# ProcessorTestBoardV2.net
KiCad netlist of a schematic drawn in EAGLE
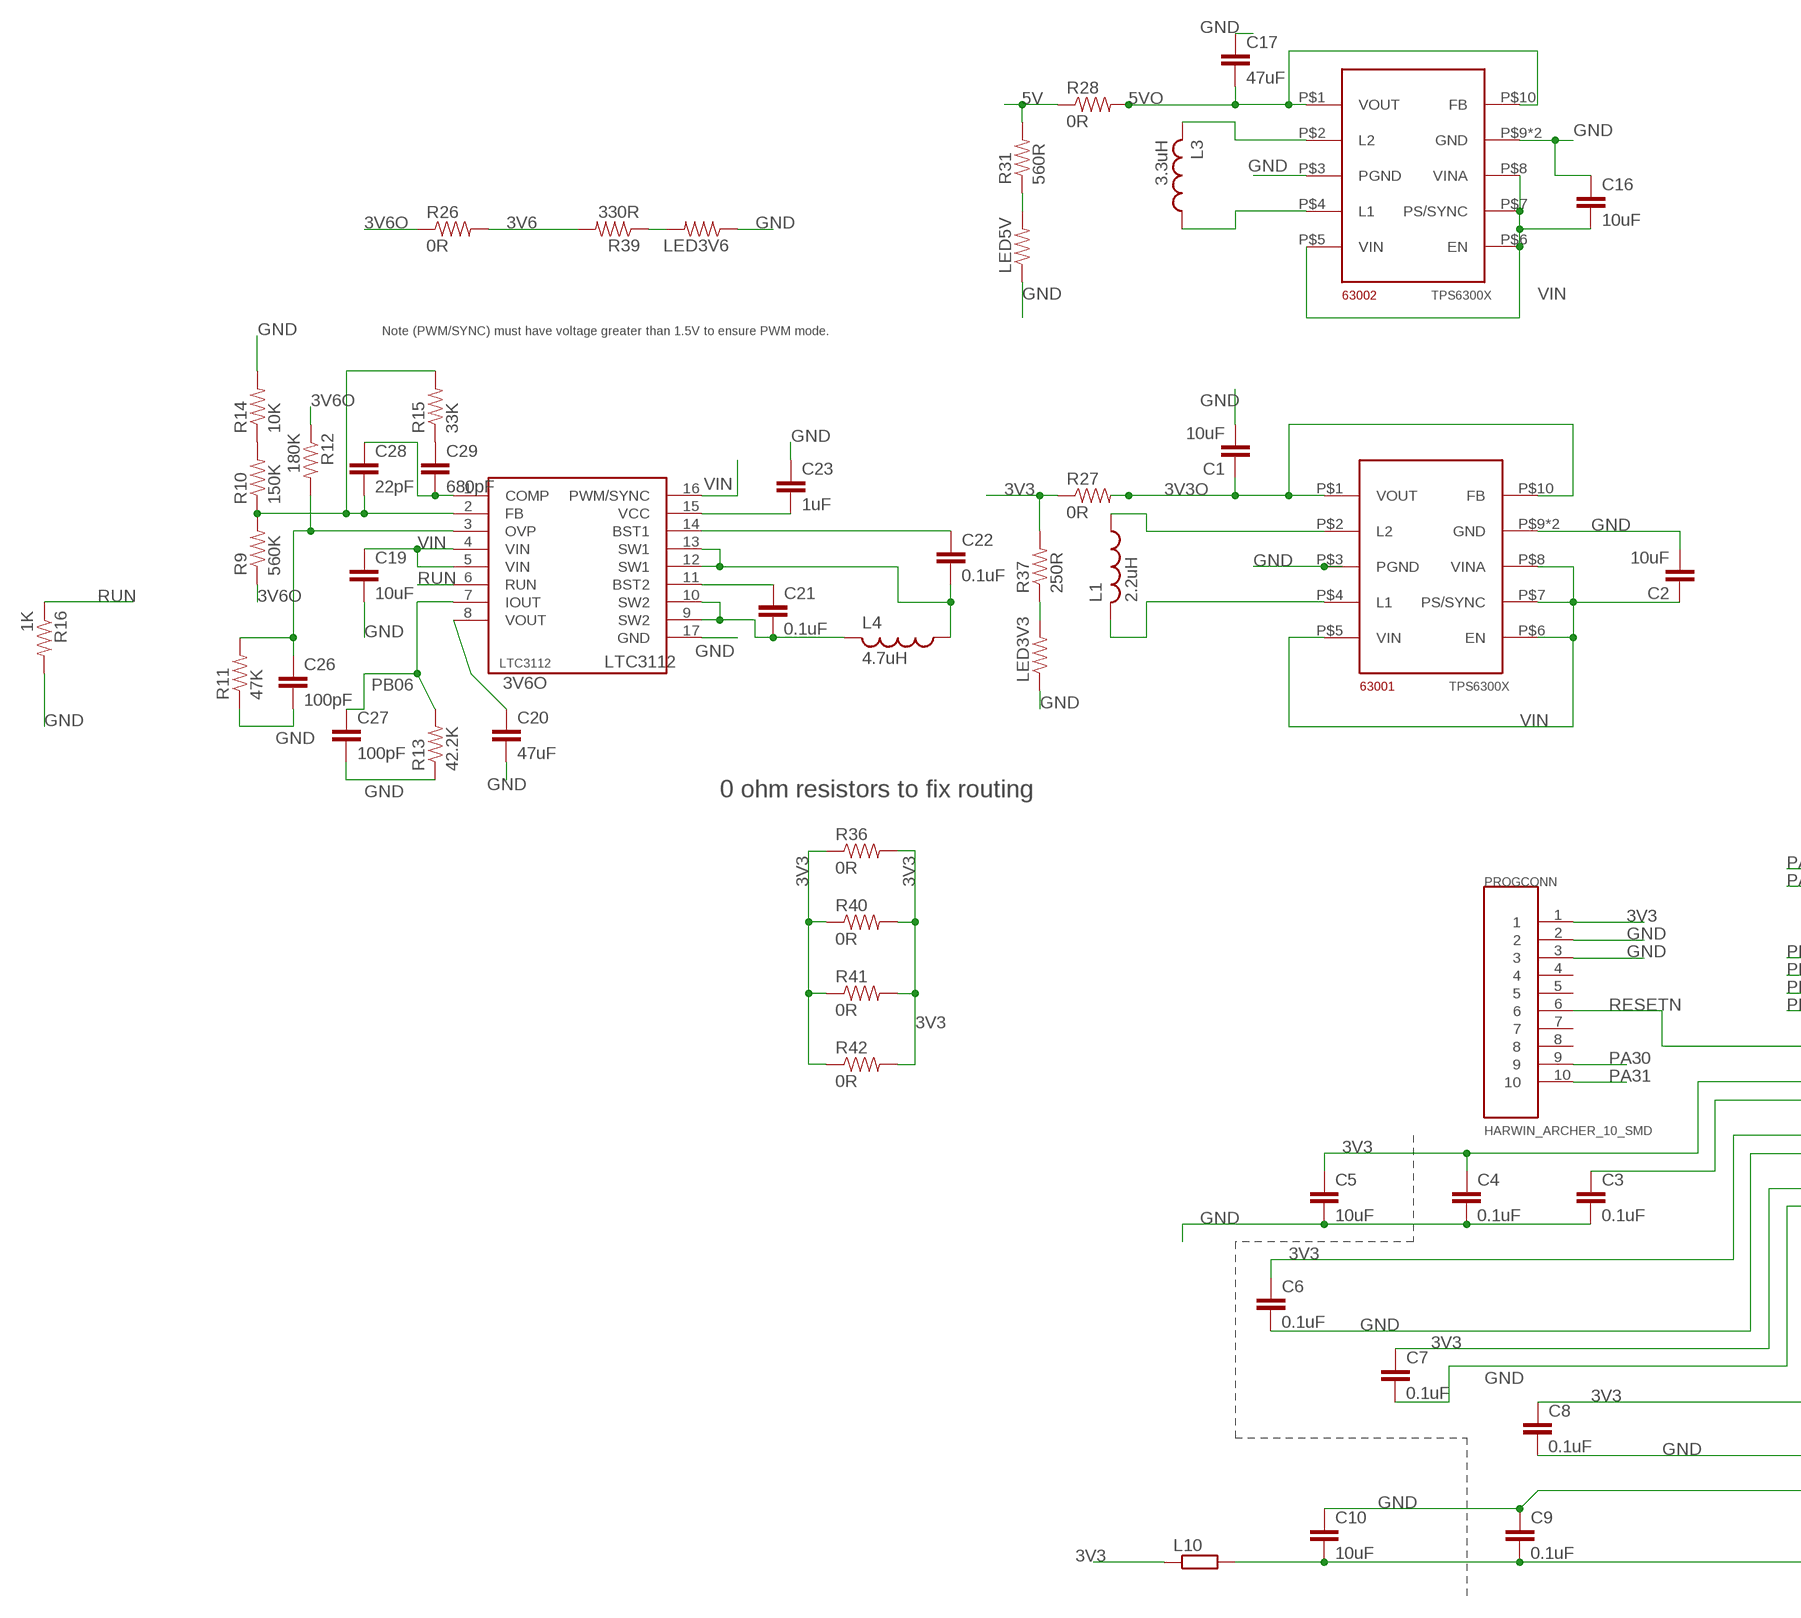
[diagram p0: schematic, sheet 1, part 1 of 2]
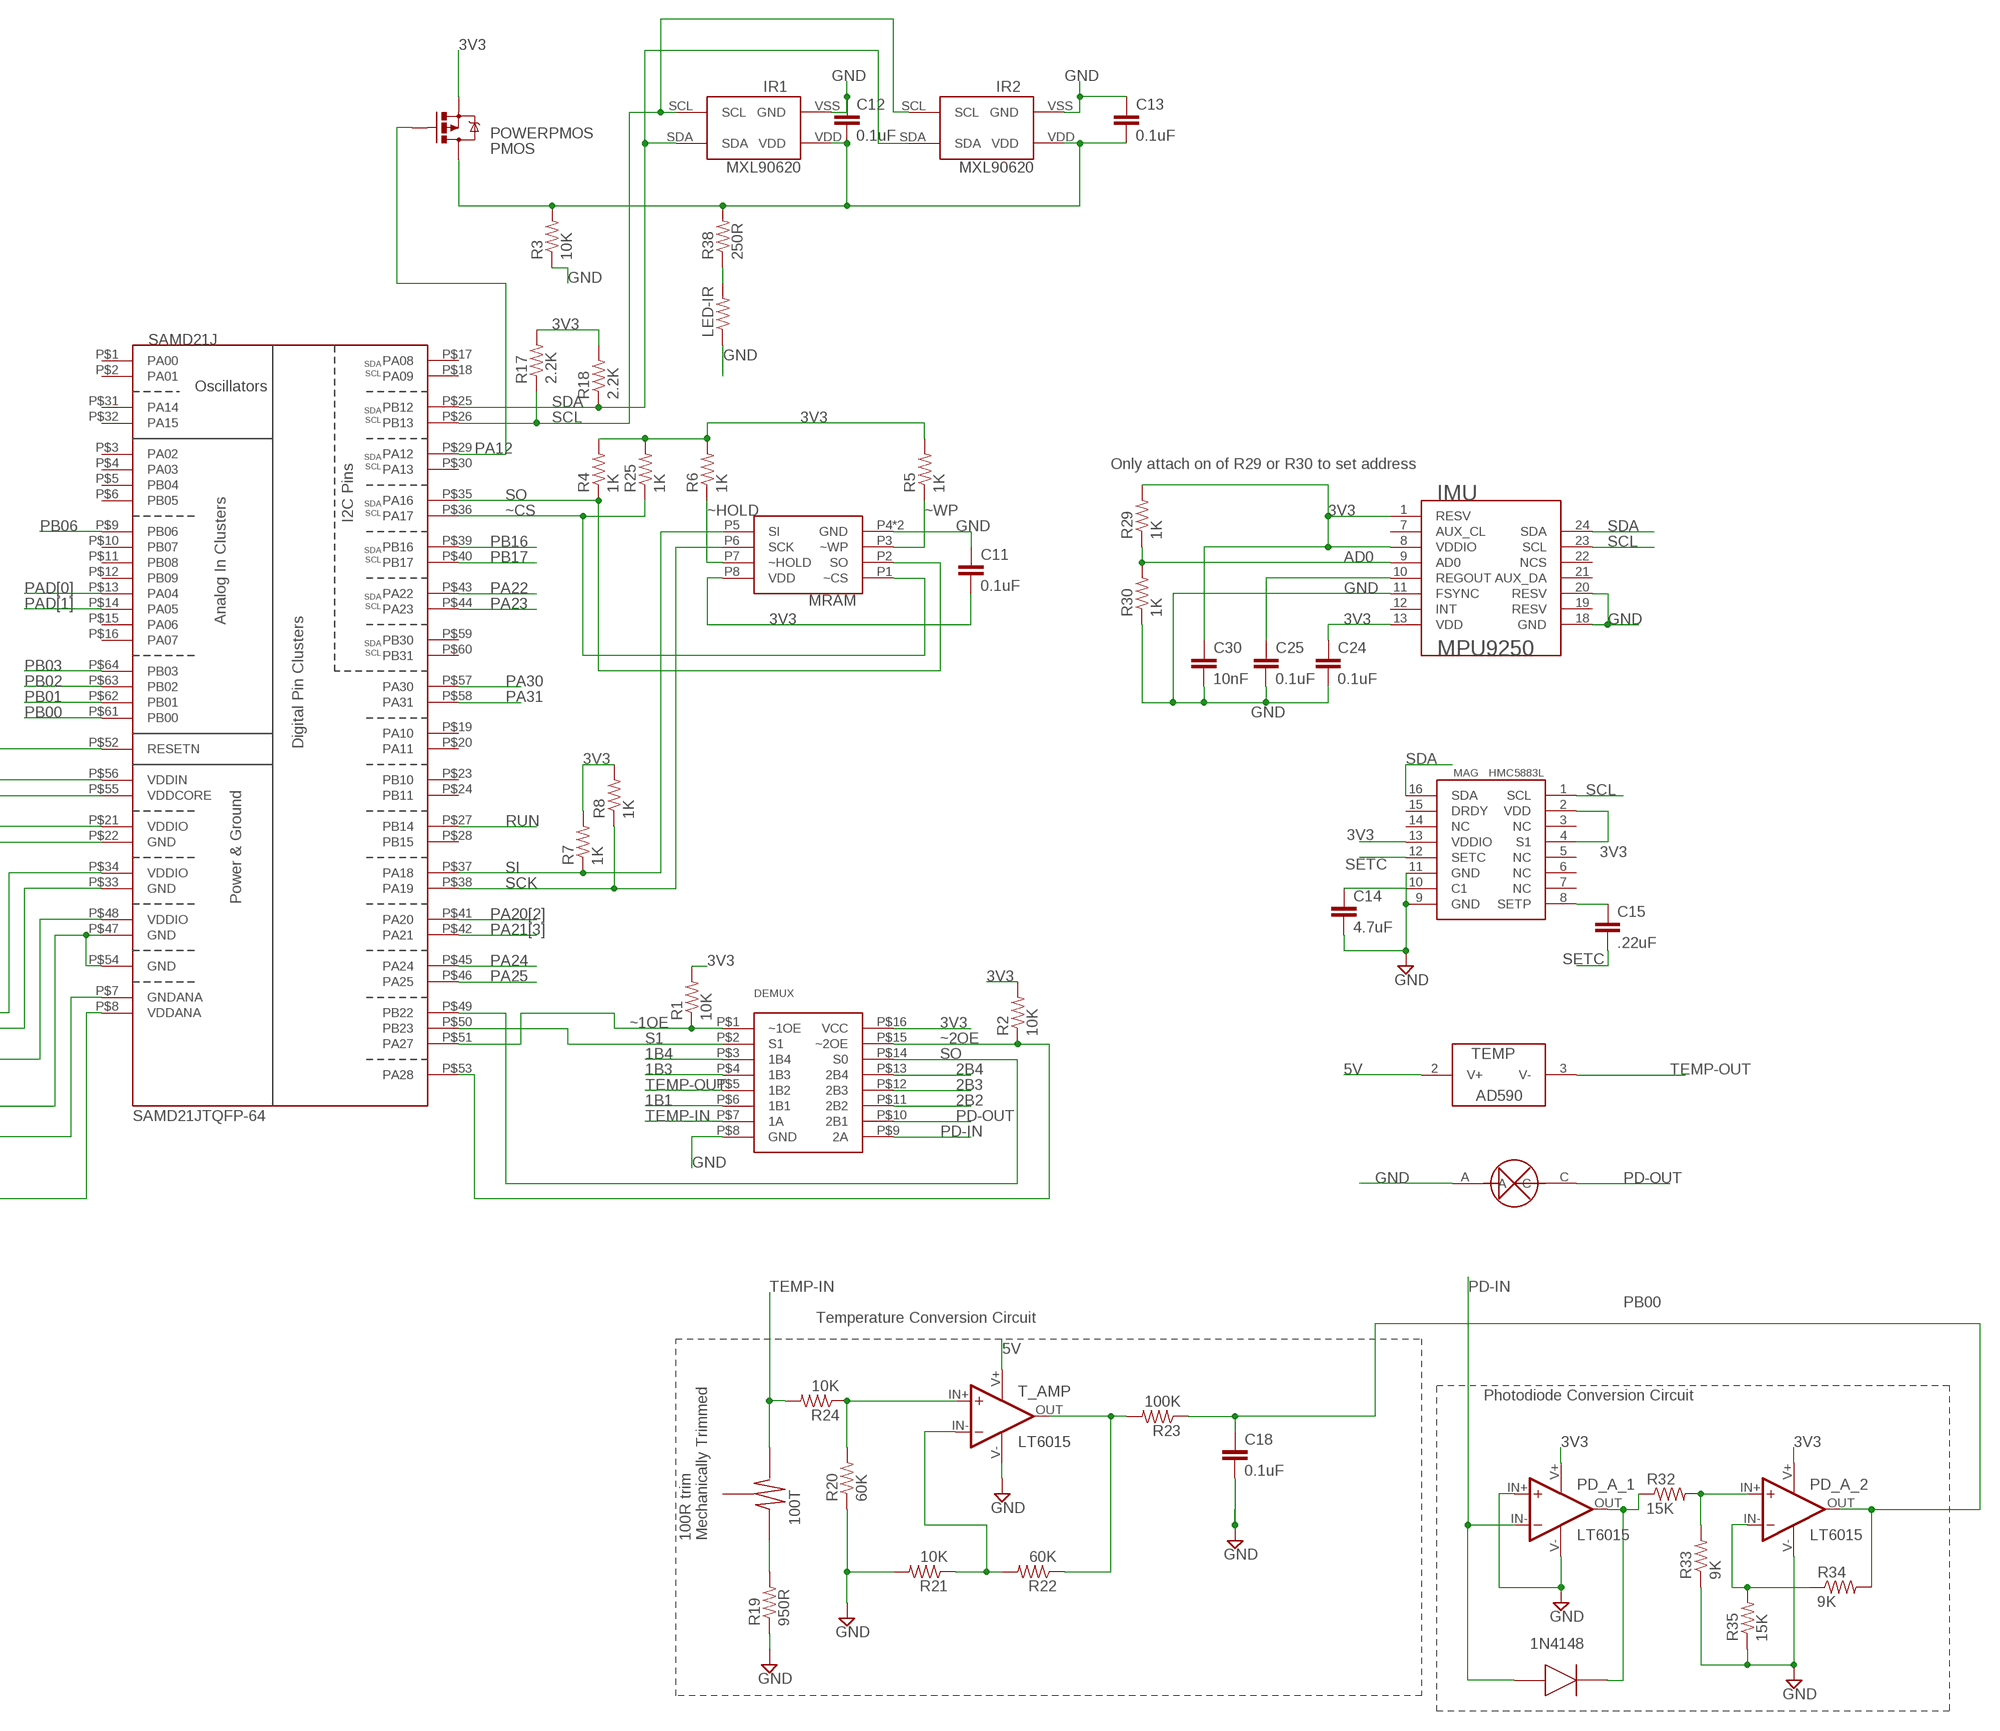
[diagram p1: schematic, sheet 1, part 2 of 2]

(export (version "E")
  (design (tool "Eeschema 10.0.6"))
  (components
    (comp (ref "1N4148")
      (value "1N4148WS")
      (footprint "eagle-import:SOD-323F")
      (libsource (lib "eagle-import") (part "1N4148WS"))
    )
    (comp (ref "100T")
      (value "TRIMPOT-TC33")
      (footprint "eagle-import:TC33X-2")
      (libsource (lib "eagle-import") (part "TRIMPOT-TC33"))
    )
    (comp (ref "63001")
      (value "TPS6300X")
      (footprint "eagle-import:QFN10_POWERPAD")
      (libsource (lib "eagle-import") (part "TPS6300X"))
    )
    (comp (ref "63002")
      (value "TPS6300X")
      (footprint "eagle-import:QFN10_POWERPAD")
      (libsource (lib "eagle-import") (part "TPS6300X"))
    )
    (comp (ref "C1")
      (value "10uF")
      (footprint "eagle-import:0805")
      (libsource (lib "eagle-import") (part "CAP0805"))
    )
    (comp (ref "C2")
      (value "10uF")
      (footprint "eagle-import:0805")
      (libsource (lib "eagle-import") (part "CAP0805"))
    )
    (comp (ref "C3")
      (value "0.1uF")
      (footprint "eagle-import:0805")
      (libsource (lib "eagle-import") (part "CAP0805"))
    )
    (comp (ref "C4")
      (value "0.1uF")
      (footprint "eagle-import:0805")
      (libsource (lib "eagle-import") (part "CAP0805"))
    )
    (comp (ref "C5")
      (value "10uF")
      (footprint "eagle-import:0805")
      (libsource (lib "eagle-import") (part "CAP0805"))
    )
    (comp (ref "C6")
      (value "0.1uF")
      (footprint "eagle-import:0805")
      (libsource (lib "eagle-import") (part "CAP0805"))
    )
    (comp (ref "C7")
      (value "0.1uF")
      (footprint "eagle-import:0805")
      (libsource (lib "eagle-import") (part "CAP0805"))
    )
    (comp (ref "C8")
      (value "0.1uF")
      (footprint "eagle-import:0805")
      (libsource (lib "eagle-import") (part "CAP0805"))
    )
    (comp (ref "C9")
      (value "0.1uF")
      (footprint "eagle-import:0805")
      (libsource (lib "eagle-import") (part "CAP0805"))
    )
    (comp (ref "C10")
      (value "10uF")
      (footprint "eagle-import:0805")
      (libsource (lib "eagle-import") (part "CAP0805"))
    )
    (comp (ref "C11")
      (value "0.1uF")
      (footprint "eagle-import:0805")
      (libsource (lib "eagle-import") (part "CAP0805"))
    )
    (comp (ref "C12")
      (value "0.1uF")
      (footprint "eagle-import:0805")
      (libsource (lib "eagle-import") (part "CAP0805"))
    )
    (comp (ref "C13")
      (value "0.1uF")
      (footprint "eagle-import:0805")
      (libsource (lib "eagle-import") (part "CAP0805"))
    )
    (comp (ref "C14")
      (value "4.7uF")
      (footprint "eagle-import:0805")
      (fields (field (name "MF") "AVX CORPORATION") (field (name "MPN") "08056D475KAT2A"))
      (libsource (lib "eagle-import") (part "CAP0805"))
    )
    (comp (ref "C15")
      (value ".22uF")
      (footprint "eagle-import:0805")
      (fields (field (name "MF") "AVX CORPORATION") (field (name "MPN") "08053C224KAT2A"))
      (libsource (lib "eagle-import") (part "CAP0805"))
    )
    (comp (ref "C16")
      (value "10uF")
      (footprint "eagle-import:0603-CAP")
      (fields (field (name "MPN") "C1608X5R1A225K080AC"))
      (libsource (lib "eagle-import") (part "CAP0603-CAP"))
    )
    (comp (ref "C17")
      (value "47uF")
      (footprint "eagle-import:0603-CAP")
      (fields (field (name "MPN") "EMK107B7474KA-T"))
      (libsource (lib "eagle-import") (part "CAP0603-CAP"))
    )
    (comp (ref "C18")
      (value "0.1uF")
      (footprint "eagle-import:0805")
      (libsource (lib "eagle-import") (part "CAP0805"))
    )
    (comp (ref "C19")
      (value "10uF")
      (footprint "eagle-import:0603-CAP")
      (libsource (lib "eagle-import") (part "CAP0603-CAP"))
    )
    (comp (ref "C20")
      (value "47uF")
      (footprint "eagle-import:0805")
      (fields (field (name "MPN") "EMK107B7474KA-T"))
      (libsource (lib "eagle-import") (part "CAP0805"))
    )
    (comp (ref "C21")
      (value "0.1uF")
      (footprint "eagle-import:0603-CAP")
      (fields (field (name "MPN") "0603YC104JAT2A"))
      (libsource (lib "eagle-import") (part "CAP0603-CAP"))
    )
    (comp (ref "C22")
      (value "0.1uF")
      (footprint "eagle-import:0603-CAP")
      (fields (field (name "MPN") "0603YC104JAT2A"))
      (libsource (lib "eagle-import") (part "CAP0603-CAP"))
    )
    (comp (ref "C23")
      (value "1uF")
      (footprint "eagle-import:0603-CAP")
      (libsource (lib "eagle-import") (part "CAP0603-CAP"))
    )
    (comp (ref "C24")
      (value "0.1uF")
      (footprint "eagle-import:0805")
      (libsource (lib "eagle-import") (part "CAP0805"))
    )
    (comp (ref "C25")
      (value "0.1uF")
      (footprint "eagle-import:0805")
      (libsource (lib "eagle-import") (part "CAP0805"))
    )
    (comp (ref "C26")
      (value "100pF")
      (footprint "eagle-import:0805")
      (fields (field (name "MF") "AVX CORPORATION") (field (name "MPN") "08051A101J4T4A"))
      (libsource (lib "eagle-import") (part "CAP0805"))
    )
    (comp (ref "C27")
      (value "100pF")
      (footprint "eagle-import:0805")
      (fields (field (name "MF") "AVX CORPORATION") (field (name "MPN") "08051A101J4T4A"))
      (libsource (lib "eagle-import") (part "CAP0805"))
    )
    (comp (ref "C28")
      (value "22pF")
      (footprint "eagle-import:0805")
      (fields (field (name "MF") "AVX CORPORATION") (field (name "MPN") "08051A220JAT2A"))
      (libsource (lib "eagle-import") (part "CAP0805"))
    )
    (comp (ref "C29")
      (value "680pF")
      (footprint "eagle-import:0805")
      (fields (field (name "MPN") "08055C681KAT2A"))
      (libsource (lib "eagle-import") (part "CAP0805"))
    )
    (comp (ref "C30")
      (value "10nF")
      (footprint "eagle-import:0805")
      (libsource (lib "eagle-import") (part "CAP0805"))
    )
    (comp (ref "DEMUX")
      (value "SN74CBTLV3253")
      (footprint "eagle-import:SOIC16R")
      (libsource (lib "eagle-import") (part "SN74CBTLV3253"))
    )
    (comp (ref "IMU")
      (value "MPU9250")
      (footprint "eagle-import:QFN-24-3X3")
      (libsource (lib "eagle-import") (part "MPU9250"))
    )
    (comp (ref "IR1")
      (value "MXL90620")
      (footprint "eagle-import:MXL90620")
      (libsource (lib "eagle-import") (part "MXL90620"))
    )
    (comp (ref "IR2")
      (value "MXL90620")
      (footprint "eagle-import:MXL90620")
      (libsource (lib "eagle-import") (part "MXL90620"))
    )
    (comp (ref "L1")
      (value "2.2uH")
      (footprint "eagle-import:L3225M")
      (libsource (lib "eagle-import") (part "L-USL3225M"))
    )
    (comp (ref "L3")
      (value "3.3uH")
      (footprint "eagle-import:L3225M")
      (fields (field (name "MPN") "JMK212BJ335KG-T"))
      (libsource (lib "eagle-import") (part "L-USL3225M"))
    )
    (comp (ref "L4")
      (value "4.7uH")
      (footprint "eagle-import:L3225M")
      (libsource (lib "eagle-import") (part "L-USL3225M"))
    )
    (comp (ref "L10")
      (value "R-EU_R0805")
      (footprint "eagle-import:R0805")
      (libsource (lib "eagle-import") (part "R-EU_R0805"))
    )
    (comp (ref "LED-IR")
      (value "RESISTOR")
      (footprint "eagle-import:0805")
      (libsource (lib "eagle-import") (part "RESISTOR"))
    )
    (comp (ref "LED3V3")
      (value "RESISTOR")
      (footprint "eagle-import:0805")
      (libsource (lib "eagle-import") (part "RESISTOR"))
    )
    (comp (ref "LED3V6")
      (value "RESISTOR")
      (footprint "eagle-import:0805")
      (libsource (lib "eagle-import") (part "RESISTOR"))
    )
    (comp (ref "LED5V")
      (value "RESISTOR")
      (footprint "eagle-import:0805")
      (libsource (lib "eagle-import") (part "RESISTOR"))
    )
    (comp (ref "LTC3112")
      (value "LTC3112")
      (footprint "eagle-import:DHD16")
      (fields (field (name "MPN") "LTC3112EFE#PBF"))
      (libsource (lib "eagle-import") (part "LTC3112"))
    )
    (comp (ref "MAG")
      (value "HMC5883L")
      (footprint "eagle-import:HMC5883L")
      (fields (field (name "MPN") "HMC5883L-TR"))
      (libsource (lib "eagle-import") (part "HMC5883L"))
    )
    (comp (ref "MRAM")
      (value "MR25H10CDC")
      (footprint "eagle-import:8PXMO-229")
      (libsource (lib "eagle-import") (part "MR25H10CDC"))
    )
    (comp (ref "PD")
      (value "PHOTODETECTOR")
      (footprint "eagle-import:PHOTODECTORDEVICE2")
      (libsource (lib "eagle-import") (part "PHOTODETECTOR"))
    )
    (comp (ref "PD_A_1")
      (value "LT6015")
      (footprint "eagle-import:SOT23-5")
      (libsource (lib "eagle-import") (part "LT6015"))
    )
    (comp (ref "PD_A_2")
      (value "LT6015")
      (footprint "eagle-import:SOT23-5")
      (libsource (lib "eagle-import") (part "LT6015"))
    )
    (comp (ref "PMOS")
      (value "POWERPMOS")
      (footprint "eagle-import:SO08")
      (libsource (lib "eagle-import") (part "POWERPMOS"))
    )
    (comp (ref "PROGCONN")
      (value "HARWIN_ARCHER_10_SMD")
      (footprint "eagle-import:HARWIN_ARCHER_10_SMD")
      (libsource (lib "eagle-import") (part "HARWIN_ARCHER_10_SMD"))
    )
    (comp (ref "R1")
      (value "10K")
      (footprint "eagle-import:0805")
      (libsource (lib "eagle-import") (part "RESISTOR"))
    )
    (comp (ref "R2")
      (value "10K")
      (footprint "eagle-import:0805")
      (libsource (lib "eagle-import") (part "RESISTOR"))
    )
    (comp (ref "R3")
      (value "10K")
      (footprint "eagle-import:0805")
      (libsource (lib "eagle-import") (part "RESISTOR"))
    )
    (comp (ref "R4")
      (value "1K")
      (footprint "eagle-import:0805")
      (libsource (lib "eagle-import") (part "RESISTOR"))
    )
    (comp (ref "R5")
      (value "1K")
      (footprint "eagle-import:0805")
      (libsource (lib "eagle-import") (part "RESISTOR"))
    )
    (comp (ref "R6")
      (value "1K")
      (footprint "eagle-import:0805")
      (libsource (lib "eagle-import") (part "RESISTOR"))
    )
    (comp (ref "R7")
      (value "1K")
      (footprint "eagle-import:0805")
      (libsource (lib "eagle-import") (part "RESISTOR"))
    )
    (comp (ref "R8")
      (value "1K")
      (footprint "eagle-import:0805")
      (libsource (lib "eagle-import") (part "RESISTOR"))
    )
    (comp (ref "R9")
      (value "560K")
      (footprint "eagle-import:0805")
      (fields (field (name "MPN") "MC01W08051560K"))
      (libsource (lib "eagle-import") (part "RESISTOR"))
    )
    (comp (ref "R10")
      (value "150K")
      (footprint "eagle-import:0805")
      (libsource (lib "eagle-import") (part "RESISTOR"))
    )
    (comp (ref "R11")
      (value "47K")
      (footprint "eagle-import:0805")
      (libsource (lib "eagle-import") (part "RESISTOR"))
    )
    (comp (ref "R12")
      (value "180K")
      (footprint "eagle-import:0805")
      (fields (field (name "MPN") "ERJ-6GEYJ184V"))
      (libsource (lib "eagle-import") (part "RESISTOR"))
    )
    (comp (ref "R13")
      (value "42.2K")
      (footprint "eagle-import:0805")
      (libsource (lib "eagle-import") (part "RESISTOR"))
    )
    (comp (ref "R14")
      (value "10K")
      (footprint "eagle-import:0805")
      (libsource (lib "eagle-import") (part "RESISTOR"))
    )
    (comp (ref "R15")
      (value "33K")
      (footprint "eagle-import:0805")
      (libsource (lib "eagle-import") (part "RESISTOR"))
    )
    (comp (ref "R16")
      (value "1K")
      (footprint "eagle-import:0805")
      (libsource (lib "eagle-import") (part "RESISTOR"))
    )
    (comp (ref "R17")
      (value "2.2K")
      (footprint "eagle-import:0805")
      (fields (field (name "MPN") "SR1-0805-222"))
      (libsource (lib "eagle-import") (part "RESISTOR"))
    )
    (comp (ref "R18")
      (value "2.2K")
      (footprint "eagle-import:0805")
      (fields (field (name "MPN") "SR1-0805-222"))
      (libsource (lib "eagle-import") (part "RESISTOR"))
    )
    (comp (ref "R19")
      (value "950R")
      (footprint "eagle-import:0805")
      (libsource (lib "eagle-import") (part "RESISTOR"))
    )
    (comp (ref "R20")
      (value "60K")
      (footprint "eagle-import:0805")
      (libsource (lib "eagle-import") (part "RESISTOR"))
    )
    (comp (ref "R21")
      (value "10K")
      (footprint "eagle-import:0805")
      (libsource (lib "eagle-import") (part "RESISTOR"))
    )
    (comp (ref "R22")
      (value "60K")
      (footprint "eagle-import:0805")
      (libsource (lib "eagle-import") (part "RESISTOR"))
    )
    (comp (ref "R23")
      (value "100K")
      (footprint "eagle-import:0805")
      (libsource (lib "eagle-import") (part "RESISTOR"))
    )
    (comp (ref "R24")
      (value "10K")
      (footprint "eagle-import:0805")
      (libsource (lib "eagle-import") (part "RESISTOR"))
    )
    (comp (ref "R25")
      (value "1K")
      (footprint "eagle-import:0805")
      (libsource (lib "eagle-import") (part "RESISTOR"))
    )
    (comp (ref "R26")
      (value "0R")
      (footprint "eagle-import:0805")
      (libsource (lib "eagle-import") (part "RESISTOR"))
    )
    (comp (ref "R27")
      (value "0R")
      (footprint "eagle-import:0805")
      (libsource (lib "eagle-import") (part "RESISTOR"))
    )
    (comp (ref "R28")
      (value "0R")
      (footprint "eagle-import:0805")
      (libsource (lib "eagle-import") (part "RESISTOR"))
    )
    (comp (ref "R29")
      (value "1K")
      (footprint "eagle-import:0805")
      (libsource (lib "eagle-import") (part "RESISTOR"))
    )
    (comp (ref "R30")
      (value "1K")
      (footprint "eagle-import:0805")
      (libsource (lib "eagle-import") (part "RESISTOR"))
    )
    (comp (ref "R31")
      (value "560R")
      (footprint "eagle-import:0805")
      (libsource (lib "eagle-import") (part "RESISTOR"))
    )
    (comp (ref "R32")
      (value "15K")
      (footprint "eagle-import:0805")
      (libsource (lib "eagle-import") (part "RESISTOR"))
    )
    (comp (ref "R33")
      (value "9K")
      (footprint "eagle-import:0805")
      (libsource (lib "eagle-import") (part "RESISTOR"))
    )
    (comp (ref "R34")
      (value "9K")
      (footprint "eagle-import:0805")
      (libsource (lib "eagle-import") (part "RESISTOR"))
    )
    (comp (ref "R35")
      (value "15K")
      (footprint "eagle-import:0805")
      (libsource (lib "eagle-import") (part "RESISTOR"))
    )
    (comp (ref "R36")
      (value "0R")
      (footprint "eagle-import:0805")
      (libsource (lib "eagle-import") (part "RESISTOR"))
    )
    (comp (ref "R37")
      (value "250R")
      (footprint "eagle-import:0805")
      (libsource (lib "eagle-import") (part "RESISTOR"))
    )
    (comp (ref "R38")
      (value "250R")
      (footprint "eagle-import:0805")
      (libsource (lib "eagle-import") (part "RESISTOR"))
    )
    (comp (ref "R39")
      (value "330R")
      (footprint "eagle-import:0805")
      (libsource (lib "eagle-import") (part "RESISTOR"))
    )
    (comp (ref "R40")
      (value "0R")
      (footprint "eagle-import:0805")
      (libsource (lib "eagle-import") (part "RESISTOR"))
    )
    (comp (ref "R41")
      (value "0R")
      (footprint "eagle-import:0805")
      (libsource (lib "eagle-import") (part "RESISTOR"))
    )
    (comp (ref "R42")
      (value "0R")
      (footprint "eagle-import:0805")
      (libsource (lib "eagle-import") (part "RESISTOR"))
    )
    (comp (ref "SAMD21J")
      (value "SAMD21JTQFP-64")
      (footprint "eagle-import:TQFP-64")
      (libsource (lib "eagle-import") (part "SAMD21JTQFP-64"))
    )
    (comp (ref "TEMP")
      (value "AD590")
      (footprint "eagle-import:8SOIC")
      (libsource (lib "eagle-import") (part "AD590-SOIC-8"))
    )
    (comp (ref "T_AMP")
      (value "LT6015")
      (footprint "eagle-import:SOT23-5")
      (libsource (lib "eagle-import") (part "LT6015"))
    )
  )
  (nets
    (net (code "1") (name "/1B1") (class "Default")
      (node (ref "DEMUX") (pin "P$6") (pinfunction "1B1_P$6") (pintype "bidirectional"))
    )
    (net (code "2") (name "/1B3") (class "Default")
      (node (ref "DEMUX") (pin "P$4") (pinfunction "1B3_P$4") (pintype "bidirectional"))
    )
    (net (code "3") (name "/1B4") (class "Default")
      (node (ref "DEMUX") (pin "P$3") (pinfunction "1B4_P$3") (pintype "bidirectional"))
    )
    (net (code "4") (name "/2B2") (class "Default")
      (node (ref "DEMUX") (pin "P$11") (pinfunction "2B2_P$11") (pintype "bidirectional"))
    )
    (net (code "5") (name "/2B3") (class "Default")
      (node (ref "DEMUX") (pin "P$12") (pinfunction "2B3_P$12") (pintype "bidirectional"))
    )
    (net (code "6") (name "/2B4") (class "Default")
      (node (ref "DEMUX") (pin "P$13") (pinfunction "2B4_P$13") (pintype "bidirectional"))
    )
    (net (code "7") (name "/3V3") (class "Default")
      (node (ref "C11") (pin "2") (pinfunction "2_2") (pintype "passive"))
      (node (ref "C24") (pin "1") (pinfunction "1_1") (pintype "passive"))
      (node (ref "C30") (pin "1") (pinfunction "1_1") (pintype "passive"))
      (node (ref "C4") (pin "1") (pinfunction "1_1") (pintype "passive"))
      (node (ref "C5") (pin "1") (pinfunction "1_1") (pintype "passive"))
      (node (ref "C6") (pin "1") (pinfunction "1_1") (pintype "passive"))
      (node (ref "C7") (pin "1") (pinfunction "1_1") (pintype "passive"))
      (node (ref "C8") (pin "1") (pinfunction "1_1") (pintype "passive"))
      (node (ref "DEMUX") (pin "P$16") (pinfunction "VCC_P$16") (pintype "bidirectional"))
      (node (ref "IMU") (pin "1") (pinfunction "RESV_1") (pintype "bidirectional"))
      (node (ref "IMU") (pin "13") (pinfunction "VDD_13") (pintype "bidirectional"))
      (node (ref "IMU") (pin "8") (pinfunction "VDDIO_8") (pintype "bidirectional"))
      (node (ref "L10") (pin "1") (pinfunction "1_1") (pintype "passive"))
      (node (ref "MAG") (pin "13") (pinfunction "VDDIO_13") (pintype "bidirectional"))
      (node (ref "MAG") (pin "2") (pinfunction "VDD_2") (pintype "bidirectional"))
      (node (ref "MAG") (pin "4") (pinfunction "S1_4") (pintype "bidirectional"))
      (node (ref "MRAM") (pin "P8") (pinfunction "VDD_P8") (pintype "bidirectional"))
      (node (ref "PD_A_1") (pin "V+") (pinfunction "V+_V+") (pintype "power_in"))
      (node (ref "PD_A_2") (pin "V+") (pinfunction "V+_V+") (pintype "power_in"))
      (node (ref "PMOS") (pin "1") (pinfunction "S_1") (pintype "passive"))
      (node (ref "PMOS") (pin "2") (pinfunction "S_2") (pintype "passive"))
      (node (ref "PMOS") (pin "3") (pinfunction "S_3") (pintype "passive"))
      (node (ref "PROGCONN") (pin "1") (pinfunction "1_1") (pintype "bidirectional"))
      (node (ref "R1") (pin "2") (pinfunction "2_2") (pintype "passive"))
      (node (ref "R17") (pin "2") (pinfunction "2_2") (pintype "passive"))
      (node (ref "R18") (pin "2") (pinfunction "2_2") (pintype "passive"))
      (node (ref "R2") (pin "2") (pinfunction "2_2") (pintype "passive"))
      (node (ref "R25") (pin "2") (pinfunction "2_2") (pintype "passive"))
      (node (ref "R27") (pin "1") (pinfunction "1_1") (pintype "passive"))
      (node (ref "R29") (pin "2") (pinfunction "2_2") (pintype "passive"))
      (node (ref "R36") (pin "1") (pinfunction "1_1") (pintype "passive"))
      (node (ref "R36") (pin "2") (pinfunction "2_2") (pintype "passive"))
      (node (ref "R37") (pin "2") (pinfunction "2_2") (pintype "passive"))
      (node (ref "R4") (pin "2") (pinfunction "2_2") (pintype "passive"))
      (node (ref "R40") (pin "1") (pinfunction "1_1") (pintype "passive"))
      (node (ref "R40") (pin "2") (pinfunction "2_2") (pintype "passive"))
      (node (ref "R41") (pin "1") (pinfunction "1_1") (pintype "passive"))
      (node (ref "R41") (pin "2") (pinfunction "2_2") (pintype "passive"))
      (node (ref "R42") (pin "1") (pinfunction "1_1") (pintype "passive"))
      (node (ref "R42") (pin "2") (pinfunction "2_2") (pintype "passive"))
      (node (ref "R5") (pin "2") (pinfunction "2_2") (pintype "passive"))
      (node (ref "R6") (pin "2") (pinfunction "2_2") (pintype "passive"))
      (node (ref "R7") (pin "2") (pinfunction "2_2") (pintype "passive"))
      (node (ref "R8") (pin "2") (pinfunction "2_2") (pintype "passive"))
      (node (ref "SAMD21J") (pin "P$21") (pinfunction "VDDIO_P$21") (pintype "power_in"))
      (node (ref "SAMD21J") (pin "P$34") (pinfunction "VDDIO_P$34") (pintype "power_in"))
      (node (ref "SAMD21J") (pin "P$48") (pinfunction "VDDIO_P$48") (pintype "power_in"))
      (node (ref "SAMD21J") (pin "P$56") (pinfunction "VDDIN_P$56") (pintype "power_in"))
    )
    (net (code "8") (name "/3V3O") (class "Default")
      (node (ref "63001") (pin "P$1") (pinfunction "VOUT_P$1") (pintype "output"))
      (node (ref "63001") (pin "P$10") (pinfunction "FB_P$10") (pintype "input"))
      (node (ref "C1") (pin "1") (pinfunction "1_1") (pintype "passive"))
      (node (ref "R27") (pin "2") (pinfunction "2_2") (pintype "passive"))
    )
    (net (code "9") (name "/3V6") (class "Default")
      (node (ref "R26") (pin "2") (pinfunction "2_2") (pintype "passive"))
      (node (ref "R39") (pin "2") (pinfunction "2_2") (pintype "passive"))
    )
    (net (code "10") (name "/3V6O") (class "Default")
      (node (ref "C20") (pin "1") (pinfunction "1_1") (pintype "passive"))
      (node (ref "LTC3112") (pin "8") (pinfunction "VOUT_8") (pintype "bidirectional"))
      (node (ref "R12") (pin "1") (pinfunction "1_1") (pintype "passive"))
      (node (ref "R26") (pin "1") (pinfunction "1_1") (pintype "passive"))
      (node (ref "R9") (pin "1") (pinfunction "1_1") (pintype "passive"))
    )
    (net (code "11") (name "/5V") (class "Default")
      (node (ref "R28") (pin "1") (pinfunction "1_1") (pintype "passive"))
      (node (ref "R31") (pin "2") (pinfunction "2_2") (pintype "passive"))
      (node (ref "TEMP") (pin "2") (pinfunction "V+_2") (pintype "bidirectional"))
      (node (ref "T_AMP") (pin "V+") (pinfunction "V+_V+") (pintype "power_in"))
    )
    (net (code "12") (name "/5VO") (class "Default")
      (node (ref "63002") (pin "P$1") (pinfunction "VOUT_P$1") (pintype "output"))
      (node (ref "63002") (pin "P$10") (pinfunction "FB_P$10") (pintype "input"))
      (node (ref "C17") (pin "2") (pinfunction "2_2") (pintype "passive"))
      (node (ref "R28") (pin "2") (pinfunction "2_2") (pintype "passive"))
    )
    (net (code "13") (name "/AD0") (class "Default")
      (node (ref "IMU") (pin "9") (pinfunction "AD0_9") (pintype "bidirectional"))
      (node (ref "R29") (pin "1") (pinfunction "1_1") (pintype "passive"))
      (node (ref "R30") (pin "2") (pinfunction "2_2") (pintype "passive"))
    )
    (net (code "14") (name "/PA12") (class "Default")
      (node (ref "PMOS") (pin "4") (pinfunction "G_4") (pintype "passive"))
      (node (ref "SAMD21J") (pin "P$29") (pinfunction "PA12_P$29") (pintype "bidirectional"))
    )
    (net (code "15") (name "/PA20[2]") (class "Default")
      (node (ref "SAMD21J") (pin "P$41") (pinfunction "PA20_P$41") (pintype "bidirectional"))
    )
    (net (code "16") (name "/PA21[3]") (class "Default")
      (node (ref "SAMD21J") (pin "P$42") (pinfunction "PA21_P$42") (pintype "bidirectional"))
    )
    (net (code "17") (name "/PA22") (class "Default")
      (node (ref "SAMD21J") (pin "P$43") (pinfunction "PA22_P$43") (pintype "bidirectional"))
    )
    (net (code "18") (name "/PA23") (class "Default")
      (node (ref "SAMD21J") (pin "P$44") (pinfunction "PA23_P$44") (pintype "bidirectional"))
    )
    (net (code "19") (name "/PA24") (class "Default")
      (node (ref "SAMD21J") (pin "P$45") (pinfunction "PA24_P$45") (pintype "bidirectional"))
    )
    (net (code "20") (name "/PA25") (class "Default")
      (node (ref "SAMD21J") (pin "P$46") (pinfunction "PA25_P$46") (pintype "bidirectional"))
    )
    (net (code "21") (name "/PA30") (class "Default")
      (node (ref "PROGCONN") (pin "9") (pinfunction "9_9") (pintype "bidirectional"))
      (node (ref "SAMD21J") (pin "P$57") (pinfunction "PA30_P$57") (pintype "bidirectional"))
    )
    (net (code "22") (name "/PA31") (class "Default")
      (node (ref "PROGCONN") (pin "10") (pinfunction "10_10") (pintype "bidirectional"))
      (node (ref "SAMD21J") (pin "P$58") (pinfunction "PA31_P$58") (pintype "bidirectional"))
    )
    (net (code "23") (name "/PAD[0]") (class "Default")
      (node (ref "SAMD21J") (pin "P$13") (pinfunction "PA04_P$13") (pintype "bidirectional"))
    )
    (net (code "24") (name "/PAD[1]") (class "Default")
      (node (ref "SAMD21J") (pin "P$14") (pinfunction "PA05_P$14") (pintype "bidirectional"))
    )
    (net (code "25") (name "/PB00") (class "Default")
      (node (ref "C18") (pin "1") (pinfunction "1_1") (pintype "passive"))
      (node (ref "PD_A_2") (pin "OUT") (pinfunction "OUT_OUT") (pintype "output"))
      (node (ref "R23") (pin "1") (pinfunction "1_1") (pintype "passive"))
      (node (ref "R34") (pin "2") (pinfunction "2_2") (pintype "passive"))
      (node (ref "SAMD21J") (pin "P$61") (pinfunction "PB00_P$61") (pintype "bidirectional"))
    )
    (net (code "26") (name "/PB01") (class "Default")
      (node (ref "SAMD21J") (pin "P$62") (pinfunction "PB01_P$62") (pintype "bidirectional"))
    )
    (net (code "27") (name "/PB02") (class "Default")
      (node (ref "SAMD21J") (pin "P$63") (pinfunction "PB02_P$63") (pintype "bidirectional"))
    )
    (net (code "28") (name "/PB03") (class "Default")
      (node (ref "SAMD21J") (pin "P$64") (pinfunction "PB03_P$64") (pintype "bidirectional"))
    )
    (net (code "29") (name "/PB06") (class "Default")
      (node (ref "C27") (pin "1") (pinfunction "1_1") (pintype "passive"))
      (node (ref "LTC3112") (pin "7") (pinfunction "IOUT_7") (pintype "bidirectional"))
      (node (ref "R13") (pin "2") (pinfunction "2_2") (pintype "passive"))
      (node (ref "SAMD21J") (pin "P$9") (pinfunction "PB06_P$9") (pintype "bidirectional"))
    )
    (net (code "30") (name "/PB16") (class "Default")
      (node (ref "SAMD21J") (pin "P$39") (pinfunction "PB16_P$39") (pintype "bidirectional"))
    )
    (net (code "31") (name "/PB17") (class "Default")
      (node (ref "SAMD21J") (pin "P$40") (pinfunction "PB17_P$40") (pintype "bidirectional"))
    )
    (net (code "32") (name "/PD-IN") (class "Default")
      (node (ref "1N4148") (pin "ANODE") (pinfunction "ANODE_ANODE") (pintype "bidirectional"))
      (node (ref "DEMUX") (pin "P$9") (pinfunction "2A_P$9") (pintype "bidirectional"))
      (node (ref "PD_A_1") (pin "IN-") (pinfunction "IN-_IN-") (pintype "input"))
    )
    (net (code "33") (name "/PD-OUT") (class "Default")
      (node (ref "DEMUX") (pin "P$10") (pinfunction "2B1_P$10") (pintype "bidirectional"))
      (node (ref "PD") (pin "C") (pinfunction "C_C") (pintype "bidirectional"))
    )
    (net (code "34") (name "/RESETN") (class "Default")
      (node (ref "PROGCONN") (pin "6") (pinfunction "6_6") (pintype "bidirectional"))
      (node (ref "SAMD21J") (pin "P$52") (pinfunction "RESETN_P$52") (pintype "input"))
    )
    (net (code "35") (name "/RUN") (class "Default")
      (node (ref "LTC3112") (pin "6") (pinfunction "RUN_6") (pintype "bidirectional"))
      (node (ref "R16") (pin "1") (pinfunction "1_1") (pintype "passive"))
      (node (ref "SAMD21J") (pin "P$27") (pinfunction "PB14_P$27") (pintype "bidirectional"))
    )
    (net (code "36") (name "/S1") (class "Default")
      (node (ref "DEMUX") (pin "P$2") (pinfunction "S1_P$2") (pintype "bidirectional"))
      (node (ref "SAMD21J") (pin "P$50") (pinfunction "PB23_P$50") (pintype "bidirectional"))
    )
    (net (code "37") (name "/SCK") (class "Default")
      (node (ref "MRAM") (pin "P6") (pinfunction "SCK_P6") (pintype "bidirectional"))
      (node (ref "R8") (pin "1") (pinfunction "1_1") (pintype "passive"))
      (node (ref "SAMD21J") (pin "P$38") (pinfunction "PA19_P$38") (pintype "bidirectional"))
    )
    (net (code "38") (name "/SCL") (class "Default")
      (node (ref "IMU") (pin "23") (pinfunction "SCL_23") (pintype "bidirectional"))
      (node (ref "IR1") (pin "SCL") (pinfunction "SCL_SCL") (pintype "bidirectional"))
      (node (ref "IR2") (pin "SCL") (pinfunction "SCL_SCL") (pintype "bidirectional"))
      (node (ref "MAG") (pin "1") (pinfunction "SCL_1") (pintype "bidirectional"))
      (node (ref "R17") (pin "1") (pinfunction "1_1") (pintype "passive"))
      (node (ref "SAMD21J") (pin "P$26") (pinfunction "PB13_P$26") (pintype "bidirectional"))
    )
    (net (code "39") (name "/SDA") (class "Default")
      (node (ref "IMU") (pin "24") (pinfunction "SDA_24") (pintype "bidirectional"))
      (node (ref "IR1") (pin "SDA") (pinfunction "SDA_SDA") (pintype "bidirectional"))
      (node (ref "IR2") (pin "SDA") (pinfunction "SDA_SDA") (pintype "bidirectional"))
      (node (ref "MAG") (pin "16") (pinfunction "SDA_16") (pintype "bidirectional"))
      (node (ref "R18") (pin "1") (pinfunction "1_1") (pintype "passive"))
      (node (ref "SAMD21J") (pin "P$25") (pinfunction "PB12_P$25") (pintype "bidirectional"))
    )
    (net (code "40") (name "/SETC") (class "Default")
      (node (ref "C15") (pin "2") (pinfunction "2_2") (pintype "passive"))
      (node (ref "MAG") (pin "12") (pinfunction "SETC_12") (pintype "bidirectional"))
    )
    (net (code "41") (name "/SI") (class "Default")
      (node (ref "MRAM") (pin "P5") (pinfunction "SI_P5") (pintype "bidirectional"))
      (node (ref "R7") (pin "1") (pinfunction "1_1") (pintype "passive"))
      (node (ref "SAMD21J") (pin "P$37") (pinfunction "PA18_P$37") (pintype "bidirectional"))
    )
    (net (code "42") (name "/SO") (class "Default")
      (node (ref "DEMUX") (pin "P$14") (pinfunction "S0_P$14") (pintype "bidirectional"))
      (node (ref "MRAM") (pin "P2") (pinfunction "SO_P2") (pintype "bidirectional"))
      (node (ref "R4") (pin "1") (pinfunction "1_1") (pintype "passive"))
      (node (ref "SAMD21J") (pin "P$35") (pinfunction "PA16_P$35") (pintype "bidirectional"))
      (node (ref "SAMD21J") (pin "P$49") (pinfunction "PB22_P$49") (pintype "bidirectional"))
    )
    (net (code "43") (name "/TEMP-IN") (class "Default")
      (node (ref "100T") (pin "P$3") (pinfunction "3_P$3") (pintype "bidirectional"))
      (node (ref "DEMUX") (pin "P$7") (pinfunction "1A_P$7") (pintype "bidirectional"))
      (node (ref "R24") (pin "2") (pinfunction "2_2") (pintype "passive"))
    )
    (net (code "44") (name "/TEMP-OUT") (class "Default")
      (node (ref "DEMUX") (pin "P$5") (pinfunction "1B2_P$5") (pintype "bidirectional"))
      (node (ref "TEMP") (pin "3") (pinfunction "V-_3") (pintype "bidirectional"))
    )
    (net (code "45") (name "/VIN") (class "Default")
      (node (ref "63001") (pin "P$5") (pinfunction "VIN_P$5") (pintype "input"))
      (node (ref "63001") (pin "P$6") (pinfunction "EN_P$6") (pintype "input"))
      (node (ref "63001") (pin "P$7") (pinfunction "PS/SYNC_P$7") (pintype "input"))
      (node (ref "63001") (pin "P$8") (pinfunction "VINA_P$8") (pintype "input"))
      (node (ref "63002") (pin "P$5") (pinfunction "VIN_P$5") (pintype "input"))
      (node (ref "63002") (pin "P$6") (pinfunction "EN_P$6") (pintype "input"))
      (node (ref "63002") (pin "P$7") (pinfunction "PS/SYNC_P$7") (pintype "input"))
      (node (ref "63002") (pin "P$8") (pinfunction "VINA_P$8") (pintype "input"))
      (node (ref "C16") (pin "2") (pinfunction "2_2") (pintype "passive"))
      (node (ref "C19") (pin "1") (pinfunction "1_1") (pintype "passive"))
      (node (ref "C2") (pin "1") (pinfunction "1_1") (pintype "passive"))
      (node (ref "LTC3112") (pin "16") (pinfunction "PWM/SYNC_16") (pintype "bidirectional"))
      (node (ref "LTC3112") (pin "4") (pinfunction "VIN_4") (pintype "bidirectional"))
      (node (ref "LTC3112") (pin "5") (pinfunction "VIN_5") (pintype "bidirectional"))
    )
    (net (code "46") (name "/~{1OE}") (class "Default")
      (node (ref "DEMUX") (pin "P$1") (pinfunction "~{1OE}_P$1") (pintype "bidirectional"))
      (node (ref "R1") (pin "1") (pinfunction "1_1") (pintype "passive"))
      (node (ref "SAMD21J") (pin "P$51") (pinfunction "PA27_P$51") (pintype "bidirectional"))
    )
    (net (code "47") (name "/~{2OE}") (class "Default")
      (node (ref "DEMUX") (pin "P$15") (pinfunction "~{2OE}_P$15") (pintype "bidirectional"))
      (node (ref "R2") (pin "1") (pinfunction "1_1") (pintype "passive"))
      (node (ref "SAMD21J") (pin "P$53") (pinfunction "PA28_P$53") (pintype "bidirectional"))
    )
    (net (code "48") (name "/~{CS}") (class "Default")
      (node (ref "MRAM") (pin "P1") (pinfunction "~{CS}_P1") (pintype "bidirectional"))
      (node (ref "R25") (pin "1") (pinfunction "1_1") (pintype "passive"))
      (node (ref "SAMD21J") (pin "P$36") (pinfunction "PA17_P$36") (pintype "bidirectional"))
    )
    (net (code "49") (name "/~{HOLD}") (class "Default")
      (node (ref "MRAM") (pin "P7") (pinfunction "~{HOLD}_P7") (pintype "bidirectional"))
      (node (ref "R6") (pin "1") (pinfunction "1_1") (pintype "passive"))
    )
    (net (code "50") (name "/~{WP}") (class "Default")
      (node (ref "MRAM") (pin "P3") (pinfunction "~{WP}_P3") (pintype "bidirectional"))
      (node (ref "R5") (pin "1") (pinfunction "1_1") (pintype "passive"))
    )
    (net (code "51") (name "GND") (class "Default")
      (node (ref "63001") (pin "P$3") (pinfunction "PGND_P$3") (pintype "input"))
      (node (ref "63001") (pin "P$9") (pinfunction "GND_P$9") (pintype "input"))
      (node (ref "63001") (pin "PAD") (pinfunction "GND_PAD") (pintype "input"))
      (node (ref "63002") (pin "P$3") (pinfunction "PGND_P$3") (pintype "input"))
      (node (ref "63002") (pin "P$9") (pinfunction "GND_P$9") (pintype "input"))
      (node (ref "63002") (pin "PAD") (pinfunction "GND_PAD") (pintype "input"))
      (node (ref "C1") (pin "2") (pinfunction "2_2") (pintype "passive"))
      (node (ref "C10") (pin "1") (pinfunction "1_1") (pintype "passive"))
      (node (ref "C11") (pin "1") (pinfunction "1_1") (pintype "passive"))
      (node (ref "C12") (pin "1") (pinfunction "1_1") (pintype "passive"))
      (node (ref "C13") (pin "1") (pinfunction "1_1") (pintype "passive"))
      (node (ref "C14") (pin "2") (pinfunction "2_2") (pintype "passive"))
      (node (ref "C16") (pin "1") (pinfunction "1_1") (pintype "passive"))
      (node (ref "C17") (pin "1") (pinfunction "1_1") (pintype "passive"))
      (node (ref "C18") (pin "2") (pinfunction "2_2") (pintype "passive"))
      (node (ref "C19") (pin "2") (pinfunction "2_2") (pintype "passive"))
      (node (ref "C2") (pin "2") (pinfunction "2_2") (pintype "passive"))
      (node (ref "C20") (pin "2") (pinfunction "2_2") (pintype "passive"))
      (node (ref "C23") (pin "1") (pinfunction "1_1") (pintype "passive"))
      (node (ref "C24") (pin "2") (pinfunction "2_2") (pintype "passive"))
      (node (ref "C25") (pin "2") (pinfunction "2_2") (pintype "passive"))
      (node (ref "C26") (pin "2") (pinfunction "2_2") (pintype "passive"))
      (node (ref "C27") (pin "2") (pinfunction "2_2") (pintype "passive"))
      (node (ref "C3") (pin "2") (pinfunction "2_2") (pintype "passive"))
      (node (ref "C30") (pin "2") (pinfunction "2_2") (pintype "passive"))
      (node (ref "C4") (pin "2") (pinfunction "2_2") (pintype "passive"))
      (node (ref "C5") (pin "2") (pinfunction "2_2") (pintype "passive"))
      (node (ref "C6") (pin "2") (pinfunction "2_2") (pintype "passive"))
      (node (ref "C7") (pin "2") (pinfunction "2_2") (pintype "passive"))
      (node (ref "C8") (pin "2") (pinfunction "2_2") (pintype "passive"))
      (node (ref "C9") (pin "1") (pinfunction "1_1") (pintype "passive"))
      (node (ref "DEMUX") (pin "P$8") (pinfunction "GND_P$8") (pintype "bidirectional"))
      (node (ref "IMU") (pin "11") (pinfunction "FSYNC_11") (pintype "bidirectional"))
      (node (ref "IMU") (pin "18") (pinfunction "GND_18") (pintype "bidirectional"))
      (node (ref "IMU") (pin "20") (pinfunction "RESV_20") (pintype "bidirectional"))
      (node (ref "IR1") (pin "VSS") (pinfunction "GND_VSS") (pintype "bidirectional"))
      (node (ref "IR2") (pin "VSS") (pinfunction "GND_VSS") (pintype "bidirectional"))
      (node (ref "LED-IR") (pin "1") (pinfunction "1_1") (pintype "passive"))
      (node (ref "LED3V3") (pin "1") (pinfunction "1_1") (pintype "passive"))
      (node (ref "LED3V6") (pin "1") (pinfunction "1_1") (pintype "passive"))
      (node (ref "LED5V") (pin "1") (pinfunction "1_1") (pintype "passive"))
      (node (ref "LTC3112") (pin "17") (pinfunction "GND_17") (pintype "bidirectional"))
      (node (ref "MAG") (pin "11") (pinfunction "GND_11") (pintype "bidirectional"))
      (node (ref "MAG") (pin "9") (pinfunction "GND_9") (pintype "bidirectional"))
      (node (ref "MRAM") (pin "P4") (pinfunction "GND_P4") (pintype "bidirectional"))
      (node (ref "MRAM") (pin "P9") (pinfunction "GND_P9") (pintype "bidirectional"))
      (node (ref "PD") (pin "A") (pinfunction "A_A") (pintype "bidirectional"))
      (node (ref "PD_A_1") (pin "IN+") (pinfunction "IN+_IN+") (pintype "input"))
      (node (ref "PD_A_1") (pin "V-") (pinfunction "V-_V-") (pintype "power_in"))
      (node (ref "PD_A_2") (pin "V-") (pinfunction "V-_V-") (pintype "power_in"))
      (node (ref "PROGCONN") (pin "2") (pinfunction "2_2") (pintype "bidirectional"))
      (node (ref "PROGCONN") (pin "3") (pinfunction "3_3") (pintype "bidirectional"))
      (node (ref "R11") (pin "1") (pinfunction "1_1") (pintype "passive"))
      (node (ref "R13") (pin "1") (pinfunction "1_1") (pintype "passive"))
      (node (ref "R14") (pin "2") (pinfunction "2_2") (pintype "passive"))
      (node (ref "R16") (pin "2") (pinfunction "2_2") (pintype "passive"))
      (node (ref "R19") (pin "1") (pinfunction "1_1") (pintype "passive"))
      (node (ref "R20") (pin "1") (pinfunction "1_1") (pintype "passive"))
      (node (ref "R21") (pin "2") (pinfunction "2_2") (pintype "passive"))
      (node (ref "R3") (pin "1") (pinfunction "1_1") (pintype "passive"))
      (node (ref "R30") (pin "1") (pinfunction "1_1") (pintype "passive"))
      (node (ref "R33") (pin "1") (pinfunction "1_1") (pintype "passive"))
      (node (ref "R35") (pin "1") (pinfunction "1_1") (pintype "passive"))
      (node (ref "SAMD21J") (pin "P$22") (pinfunction "GND_P$22") (pintype "power_in"))
      (node (ref "SAMD21J") (pin "P$33") (pinfunction "GND_P$33") (pintype "power_in"))
      (node (ref "SAMD21J") (pin "P$47") (pinfunction "GND_P$47") (pintype "power_in"))
      (node (ref "SAMD21J") (pin "P$54") (pinfunction "GND_P$54") (pintype "power_in"))
      (node (ref "SAMD21J") (pin "P$7") (pinfunction "GNDANA_P$7") (pintype "power_in"))
      (node (ref "T_AMP") (pin "V-") (pinfunction "V-_V-") (pintype "power_in"))
    )
    (net (code "52") (name "Net-(1N4148-PadCATHODE)") (class "Default")
      (node (ref "1N4148") (pin "CATHODE") (pinfunction "CATHODE_CATHODE") (pintype "bidirectional"))
      (node (ref "PD_A_1") (pin "OUT") (pinfunction "OUT_OUT") (pintype "output"))
      (node (ref "R32") (pin "1") (pinfunction "1_1") (pintype "passive"))
    )
    (net (code "53") (name "Net-(100T-1)") (class "Default")
      (node (ref "100T") (pin "P$1") (pinfunction "1_P$1") (pintype "bidirectional"))
      (node (ref "R19") (pin "2") (pinfunction "2_2") (pintype "passive"))
    )
    (net (code "54") (name "Net-(63001-L1)") (class "Default")
      (node (ref "63001") (pin "P$4") (pinfunction "L1_P$4") (pintype "input"))
      (node (ref "L1") (pin "2") (pinfunction "2_2") (pintype "passive"))
    )
    (net (code "55") (name "Net-(63001-L2)") (class "Default")
      (node (ref "63001") (pin "P$2") (pinfunction "L2_P$2") (pintype "input"))
      (node (ref "L1") (pin "1") (pinfunction "1_1") (pintype "passive"))
    )
    (net (code "56") (name "Net-(63002-L1)") (class "Default")
      (node (ref "63002") (pin "P$4") (pinfunction "L1_P$4") (pintype "input"))
      (node (ref "L3") (pin "1") (pinfunction "1_1") (pintype "passive"))
    )
    (net (code "57") (name "Net-(63002-L2)") (class "Default")
      (node (ref "63002") (pin "P$2") (pinfunction "L2_P$2") (pintype "input"))
      (node (ref "L3") (pin "2") (pinfunction "2_2") (pintype "passive"))
    )
    (net (code "58") (name "Net-(C12-Pad2)") (class "Default")
      (node (ref "C12") (pin "2") (pinfunction "2_2") (pintype "passive"))
      (node (ref "C13") (pin "2") (pinfunction "2_2") (pintype "passive"))
      (node (ref "IR1") (pin "VDD") (pinfunction "VDD_VDD") (pintype "bidirectional"))
      (node (ref "IR2") (pin "VDD") (pinfunction "VDD_VDD") (pintype "bidirectional"))
      (node (ref "PMOS") (pin "5") (pinfunction "D_5") (pintype "passive"))
      (node (ref "PMOS") (pin "6") (pinfunction "D_6") (pintype "passive"))
      (node (ref "PMOS") (pin "7") (pinfunction "D_7") (pintype "passive"))
      (node (ref "PMOS") (pin "8") (pinfunction "D_8") (pintype "passive"))
      (node (ref "R3") (pin "2") (pinfunction "2_2") (pintype "passive"))
      (node (ref "R38") (pin "2") (pinfunction "2_2") (pintype "passive"))
    )
    (net (code "59") (name "Net-(C21-Pad2)") (class "Default")
      (node (ref "C21") (pin "2") (pinfunction "2_2") (pintype "passive"))
      (node (ref "L4") (pin "2") (pinfunction "2_2") (pintype "passive"))
      (node (ref "LTC3112") (pin "10") (pinfunction "SW2_10") (pintype "bidirectional"))
      (node (ref "LTC3112") (pin "9") (pinfunction "SW2_9") (pintype "bidirectional"))
    )
    (net (code "60") (name "Net-(C22-Pad2)") (class "Default")
      (node (ref "C22") (pin "2") (pinfunction "2_2") (pintype "passive"))
      (node (ref "L4") (pin "1") (pinfunction "1_1") (pintype "passive"))
      (node (ref "LTC3112") (pin "12") (pinfunction "SW1_12") (pintype "bidirectional"))
      (node (ref "LTC3112") (pin "13") (pinfunction "SW1_13") (pintype "bidirectional"))
    )
    (net (code "61") (name "Net-(C29-Pad1)") (class "Default")
      (node (ref "C29") (pin "1") (pinfunction "1_1") (pintype "passive"))
      (node (ref "R15") (pin "1") (pinfunction "1_1") (pintype "passive"))
    )
    (net (code "62") (name "Net-(IMU-REGOUT)") (class "Default")
      (node (ref "C25") (pin "1") (pinfunction "1_1") (pintype "passive"))
      (node (ref "IMU") (pin "10") (pinfunction "REGOUT_10") (pintype "bidirectional"))
    )
    (net (code "63") (name "Net-(LED-IR-Pad2)") (class "Default")
      (node (ref "LED-IR") (pin "2") (pinfunction "2_2") (pintype "passive"))
      (node (ref "R38") (pin "1") (pinfunction "1_1") (pintype "passive"))
    )
    (net (code "64") (name "Net-(LED3V3-Pad2)") (class "Default")
      (node (ref "LED3V3") (pin "2") (pinfunction "2_2") (pintype "passive"))
      (node (ref "R37") (pin "1") (pinfunction "1_1") (pintype "passive"))
    )
    (net (code "65") (name "Net-(LED3V6-Pad2)") (class "Default")
      (node (ref "LED3V6") (pin "2") (pinfunction "2_2") (pintype "passive"))
      (node (ref "R39") (pin "1") (pinfunction "1_1") (pintype "passive"))
    )
    (net (code "66") (name "Net-(LED5V-Pad2)") (class "Default")
      (node (ref "LED5V") (pin "2") (pinfunction "2_2") (pintype "passive"))
      (node (ref "R31") (pin "1") (pinfunction "1_1") (pintype "passive"))
    )
    (net (code "67") (name "Net-(LTC3112-BST1)") (class "Default")
      (node (ref "C22") (pin "1") (pinfunction "1_1") (pintype "passive"))
      (node (ref "LTC3112") (pin "14") (pinfunction "BST1_14") (pintype "bidirectional"))
    )
    (net (code "68") (name "Net-(LTC3112-BST2)") (class "Default")
      (node (ref "C21") (pin "1") (pinfunction "1_1") (pintype "passive"))
      (node (ref "LTC3112") (pin "11") (pinfunction "BST2_11") (pintype "bidirectional"))
    )
    (net (code "69") (name "Net-(LTC3112-COMP)") (class "Default")
      (node (ref "C28") (pin "1") (pinfunction "1_1") (pintype "passive"))
      (node (ref "C29") (pin "2") (pinfunction "2_2") (pintype "passive"))
      (node (ref "LTC3112") (pin "1") (pinfunction "COMP_1") (pintype "bidirectional"))
    )
    (net (code "70") (name "Net-(LTC3112-FB)") (class "Default")
      (node (ref "C28") (pin "2") (pinfunction "2_2") (pintype "passive"))
      (node (ref "LTC3112") (pin "2") (pinfunction "FB_2") (pintype "bidirectional"))
      (node (ref "R10") (pin "1") (pinfunction "1_1") (pintype "passive"))
      (node (ref "R15") (pin "2") (pinfunction "2_2") (pintype "passive"))
      (node (ref "R9") (pin "2") (pinfunction "2_2") (pintype "passive"))
    )
    (net (code "71") (name "Net-(LTC3112-OVP)") (class "Default")
      (node (ref "C26") (pin "1") (pinfunction "1_1") (pintype "passive"))
      (node (ref "LTC3112") (pin "3") (pinfunction "OVP_3") (pintype "bidirectional"))
      (node (ref "R11") (pin "2") (pinfunction "2_2") (pintype "passive"))
      (node (ref "R12") (pin "2") (pinfunction "2_2") (pintype "passive"))
    )
    (net (code "72") (name "Net-(LTC3112-VCC)") (class "Default")
      (node (ref "C23") (pin "2") (pinfunction "2_2") (pintype "passive"))
      (node (ref "LTC3112") (pin "15") (pinfunction "VCC_15") (pintype "bidirectional"))
    )
    (net (code "73") (name "Net-(MAG-C1)") (class "Default")
      (node (ref "C14") (pin "1") (pinfunction "1_1") (pintype "passive"))
      (node (ref "MAG") (pin "10") (pinfunction "C1_10") (pintype "bidirectional"))
    )
    (net (code "74") (name "Net-(MAG-SETP)") (class "Default")
      (node (ref "C15") (pin "1") (pinfunction "1_1") (pintype "passive"))
      (node (ref "MAG") (pin "8") (pinfunction "SETP_8") (pintype "bidirectional"))
    )
    (net (code "75") (name "Net-(PD_A_2-PadIN+)") (class "Default")
      (node (ref "PD_A_2") (pin "IN+") (pinfunction "IN+_IN+") (pintype "input"))
      (node (ref "R32") (pin "2") (pinfunction "2_2") (pintype "passive"))
      (node (ref "R33") (pin "2") (pinfunction "2_2") (pintype "passive"))
    )
    (net (code "76") (name "Net-(PD_A_2-PadIN-)") (class "Default")
      (node (ref "PD_A_2") (pin "IN-") (pinfunction "IN-_IN-") (pintype "input"))
      (node (ref "R34") (pin "1") (pinfunction "1_1") (pintype "passive"))
      (node (ref "R35") (pin "2") (pinfunction "2_2") (pintype "passive"))
    )
    (net (code "77") (name "Net-(R10-Pad2)") (class "Default")
      (node (ref "R10") (pin "2") (pinfunction "2_2") (pintype "passive"))
      (node (ref "R14") (pin "1") (pinfunction "1_1") (pintype "passive"))
    )
    (net (code "78") (name "Net-(R20-Pad2)") (class "Default")
      (node (ref "R20") (pin "2") (pinfunction "2_2") (pintype "passive"))
      (node (ref "R24") (pin "1") (pinfunction "1_1") (pintype "passive"))
      (node (ref "T_AMP") (pin "IN+") (pinfunction "IN+_IN+") (pintype "input"))
    )
    (net (code "79") (name "Net-(R21-Pad1)") (class "Default")
      (node (ref "R21") (pin "1") (pinfunction "1_1") (pintype "passive"))
      (node (ref "R22") (pin "2") (pinfunction "2_2") (pintype "passive"))
      (node (ref "T_AMP") (pin "IN-") (pinfunction "IN-_IN-") (pintype "input"))
    )
    (net (code "80") (name "Net-(R22-Pad1)") (class "Default")
      (node (ref "R22") (pin "1") (pinfunction "1_1") (pintype "passive"))
      (node (ref "R23") (pin "2") (pinfunction "2_2") (pintype "passive"))
      (node (ref "T_AMP") (pin "OUT") (pinfunction "OUT_OUT") (pintype "output"))
    )
    (net (code "81") (name "Net-(SAMD21J-VDDANA)") (class "Default")
      (node (ref "C10") (pin "2") (pinfunction "2_2") (pintype "passive"))
      (node (ref "C9") (pin "2") (pinfunction "2_2") (pintype "passive"))
      (node (ref "L10") (pin "2") (pinfunction "2_2") (pintype "passive"))
      (node (ref "SAMD21J") (pin "P$8") (pinfunction "VDDANA_P$8") (pintype "power_in"))
    )
    (net (code "82") (name "Net-(SAMD21J-VDDCORE)") (class "Default")
      (node (ref "C3") (pin "1") (pinfunction "1_1") (pintype "passive"))
      (node (ref "SAMD21J") (pin "P$55") (pinfunction "VDDCORE_P$55") (pintype "power_in"))
    )
    (net (code "83") (name "unconnected-(100T-2-PadP$2)") (class "Default")
      (node (ref "100T") (pin "P$2") (pinfunction "2_P$2") (pintype "bidirectional"))
    )
    (net (code "84") (name "unconnected-(IMU-AUX_CL-Pad7)") (class "Default")
      (node (ref "IMU") (pin "7") (pinfunction "AUX_CL_7") (pintype "bidirectional"))
    )
    (net (code "85") (name "unconnected-(IMU-AUX_DA-Pad21)") (class "Default")
      (node (ref "IMU") (pin "21") (pinfunction "AUX_DA_21") (pintype "bidirectional"))
    )
    (net (code "86") (name "unconnected-(IMU-INT-Pad12)") (class "Default")
      (node (ref "IMU") (pin "12") (pinfunction "INT_12") (pintype "bidirectional"))
    )
    (net (code "87") (name "unconnected-(IMU-NCS-Pad22)") (class "Default")
      (node (ref "IMU") (pin "22") (pinfunction "NCS_22") (pintype "bidirectional"))
    )
    (net (code "88") (name "unconnected-(IMU-RESV-Pad19)") (class "Default")
      (node (ref "IMU") (pin "19") (pinfunction "RESV_19") (pintype "bidirectional"))
    )
    (net (code "89") (name "unconnected-(MAG-DRDY-Pad15)") (class "Default")
      (node (ref "MAG") (pin "15") (pinfunction "DRDY_15") (pintype "bidirectional"))
    )
    (net (code "90") (name "unconnected-(MAG-NC-Pad3)") (class "Default")
      (node (ref "MAG") (pin "3") (pinfunction "NC_3") (pintype "bidirectional"))
    )
    (net (code "91") (name "unconnected-(MAG-NC-Pad5)") (class "Default")
      (node (ref "MAG") (pin "5") (pinfunction "NC_5") (pintype "bidirectional"))
    )
    (net (code "92") (name "unconnected-(MAG-NC-Pad6)") (class "Default")
      (node (ref "MAG") (pin "6") (pinfunction "NC_6") (pintype "bidirectional"))
    )
    (net (code "93") (name "unconnected-(MAG-NC-Pad7)") (class "Default")
      (node (ref "MAG") (pin "7") (pinfunction "NC_7") (pintype "bidirectional"))
    )
    (net (code "94") (name "unconnected-(MAG-NC-Pad14)") (class "Default")
      (node (ref "MAG") (pin "14") (pinfunction "NC_14") (pintype "bidirectional"))
    )
    (net (code "95") (name "unconnected-(PROGCONN-Pad4)") (class "Default")
      (node (ref "PROGCONN") (pin "4") (pinfunction "4_4") (pintype "bidirectional"))
    )
    (net (code "96") (name "unconnected-(PROGCONN-Pad5)") (class "Default")
      (node (ref "PROGCONN") (pin "5") (pinfunction "5_5") (pintype "bidirectional"))
    )
    (net (code "97") (name "unconnected-(PROGCONN-Pad7)") (class "Default")
      (node (ref "PROGCONN") (pin "7") (pinfunction "7_7") (pintype "bidirectional"))
    )
    (net (code "98") (name "unconnected-(PROGCONN-Pad8)") (class "Default")
      (node (ref "PROGCONN") (pin "8") (pinfunction "8_8") (pintype "bidirectional"))
    )
    (net (code "99") (name "unconnected-(SAMD21J-PA00-PadP$1)") (class "Default")
      (node (ref "SAMD21J") (pin "P$1") (pinfunction "PA00_P$1") (pintype "bidirectional"))
    )
    (net (code "100") (name "unconnected-(SAMD21J-PA01-PadP$2)") (class "Default")
      (node (ref "SAMD21J") (pin "P$2") (pinfunction "PA01_P$2") (pintype "bidirectional"))
    )
    (net (code "101") (name "unconnected-(SAMD21J-PA02-PadP$3)") (class "Default")
      (node (ref "SAMD21J") (pin "P$3") (pinfunction "PA02_P$3") (pintype "bidirectional"))
    )
    (net (code "102") (name "unconnected-(SAMD21J-PA03-PadP$4)") (class "Default")
      (node (ref "SAMD21J") (pin "P$4") (pinfunction "PA03_P$4") (pintype "bidirectional"))
    )
    (net (code "103") (name "unconnected-(SAMD21J-PA06-PadP$15)") (class "Default")
      (node (ref "SAMD21J") (pin "P$15") (pinfunction "PA06_P$15") (pintype "bidirectional"))
    )
    (net (code "104") (name "unconnected-(SAMD21J-PA07-PadP$16)") (class "Default")
      (node (ref "SAMD21J") (pin "P$16") (pinfunction "PA07_P$16") (pintype "bidirectional"))
    )
    (net (code "105") (name "unconnected-(SAMD21J-PA08-PadP$17)") (class "Default")
      (node (ref "SAMD21J") (pin "P$17") (pinfunction "PA08_P$17") (pintype "bidirectional"))
    )
    (net (code "106") (name "unconnected-(SAMD21J-PA09-PadP$18)") (class "Default")
      (node (ref "SAMD21J") (pin "P$18") (pinfunction "PA09_P$18") (pintype "bidirectional"))
    )
    (net (code "107") (name "unconnected-(SAMD21J-PA10-PadP$19)") (class "Default")
      (node (ref "SAMD21J") (pin "P$19") (pinfunction "PA10_P$19") (pintype "bidirectional"))
    )
    (net (code "108") (name "unconnected-(SAMD21J-PA11-PadP$20)") (class "Default")
      (node (ref "SAMD21J") (pin "P$20") (pinfunction "PA11_P$20") (pintype "bidirectional"))
    )
    (net (code "109") (name "unconnected-(SAMD21J-PA13-PadP$30)") (class "Default")
      (node (ref "SAMD21J") (pin "P$30") (pinfunction "PA13_P$30") (pintype "bidirectional"))
    )
    (net (code "110") (name "unconnected-(SAMD21J-PA14-PadP$31)") (class "Default")
      (node (ref "SAMD21J") (pin "P$31") (pinfunction "PA14_P$31") (pintype "bidirectional"))
    )
    (net (code "111") (name "unconnected-(SAMD21J-PA15-PadP$32)") (class "Default")
      (node (ref "SAMD21J") (pin "P$32") (pinfunction "PA15_P$32") (pintype "bidirectional"))
    )
    (net (code "112") (name "unconnected-(SAMD21J-PB04-PadP$5)") (class "Default")
      (node (ref "SAMD21J") (pin "P$5") (pinfunction "PB04_P$5") (pintype "bidirectional"))
    )
    (net (code "113") (name "unconnected-(SAMD21J-PB05-PadP$6)") (class "Default")
      (node (ref "SAMD21J") (pin "P$6") (pinfunction "PB05_P$6") (pintype "bidirectional"))
    )
    (net (code "114") (name "unconnected-(SAMD21J-PB07-PadP$10)") (class "Default")
      (node (ref "SAMD21J") (pin "P$10") (pinfunction "PB07_P$10") (pintype "bidirectional"))
    )
    (net (code "115") (name "unconnected-(SAMD21J-PB08-PadP$11)") (class "Default")
      (node (ref "SAMD21J") (pin "P$11") (pinfunction "PB08_P$11") (pintype "bidirectional"))
    )
    (net (code "116") (name "unconnected-(SAMD21J-PB09-PadP$12)") (class "Default")
      (node (ref "SAMD21J") (pin "P$12") (pinfunction "PB09_P$12") (pintype "bidirectional"))
    )
    (net (code "117") (name "unconnected-(SAMD21J-PB10-PadP$23)") (class "Default")
      (node (ref "SAMD21J") (pin "P$23") (pinfunction "PB10_P$23") (pintype "bidirectional"))
    )
    (net (code "118") (name "unconnected-(SAMD21J-PB11-PadP$24)") (class "Default")
      (node (ref "SAMD21J") (pin "P$24") (pinfunction "PB11_P$24") (pintype "bidirectional"))
    )
    (net (code "119") (name "unconnected-(SAMD21J-PB15-PadP$28)") (class "Default")
      (node (ref "SAMD21J") (pin "P$28") (pinfunction "PB15_P$28") (pintype "bidirectional"))
    )
    (net (code "120") (name "unconnected-(SAMD21J-PB30-PadP$59)") (class "Default")
      (node (ref "SAMD21J") (pin "P$59") (pinfunction "PB30_P$59") (pintype "bidirectional"))
    )
    (net (code "121") (name "unconnected-(SAMD21J-PB31-PadP$60)") (class "Default")
      (node (ref "SAMD21J") (pin "P$60") (pinfunction "PB31_P$60") (pintype "bidirectional"))
    )
  )
)
